# power.net
KiCad netlist of a schematic drawn in Altium Designer
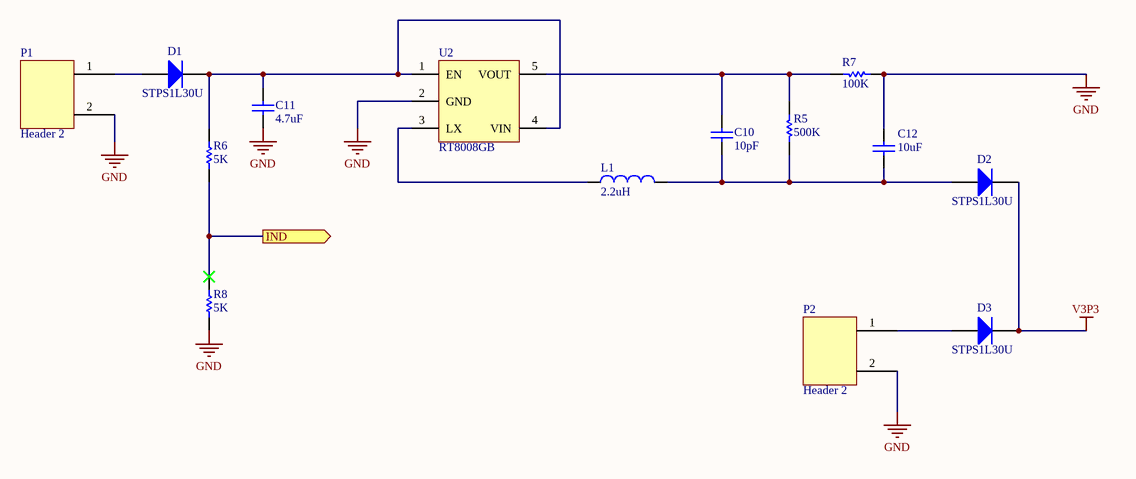
[diagram p0: power.SchDoc]

(export (version "E")
  (design (tool "Eeschema 10.0.6"))
  (components
    (comp (ref "C10")
      (value "10pF")
      (footprint "CAPACITOR")
      (description "Capacitor")
      (fields (field (name "PUBLISHER") "Altium Limited"))
      (libsource (lib "Miscellaneous Devices") (part "Cap"))
    )
    (comp (ref "C11")
      (value "4.7uF")
      (footprint "CAPACITOR")
      (description "Capacitor")
      (fields (field (name "PUBLISHER") "Altium Limited"))
      (libsource (lib "Miscellaneous Devices") (part "Cap"))
    )
    (comp (ref "C12")
      (value "10uF")
      (footprint "CAPACITOR")
      (description "Capacitor")
      (fields (field (name "PUBLISHER") "Altium Limited"))
      (libsource (lib "Miscellaneous Devices") (part "Cap"))
    )
    (comp (ref "D1")
      (value "STPS1L30U")
      (footprint "Schottky")
      (description "Diode Schottky")
      (fields (field (name "PUBLISHER") "Altium Limited"))
      (libsource (lib "Miscellaneous Devices") (part "Diode"))
    )
    (comp (ref "D2")
      (value "STPS1L30U")
      (footprint "Schottky")
      (description "Diode Schottky")
      (fields (field (name "PUBLISHER") "Altium Limited"))
      (libsource (lib "Miscellaneous Devices") (part "Diode"))
    )
    (comp (ref "D3")
      (value "STPS1L30U")
      (footprint "Schottky")
      (description "Diode Schottky")
      (fields (field (name "PUBLISHER") "Altium Limited"))
      (libsource (lib "Miscellaneous Devices") (part "Diode"))
    )
    (comp (ref "L1")
      (value "2.2uH")
      (footprint "Inductor")
      (description "Inductor")
      (fields (field (name "PUBLISHER") "Altium Limited"))
      (libsource (lib "Miscellaneous Devices") (part "Inductor"))
    )
    (comp (ref "P1")
      (value "Header 2")
      (footprint "Header 2 BATTERY")
      (libsource (lib "Klotz") (part "Header 2"))
    )
    (comp (ref "P2")
      (value "Header 2")
      (footprint "Header 2 BATTERY")
      (libsource (lib "Klotz") (part "Header 2"))
    )
    (comp (ref "R5")
      (value "500K")
      (footprint "Resistor")
      (description "Resistor")
      (fields (field (name "PUBLISHER") "Altium Limited"))
      (libsource (lib "Miscellaneous Devices") (part "Res1"))
    )
    (comp (ref "R6")
      (value "5K")
      (footprint "Resistor")
      (description "Resistor")
      (fields (field (name "PUBLISHER") "Altium Limited"))
      (libsource (lib "Miscellaneous Devices") (part "Res1"))
    )
    (comp (ref "R7")
      (value "100K")
      (footprint "Resistor")
      (description "Resistor")
      (fields (field (name "PUBLISHER") "Altium Limited"))
      (libsource (lib "Miscellaneous Devices") (part "Res1"))
    )
    (comp (ref "R8")
      (value "5K")
      (footprint "Resistor")
      (description "Resistor")
      (fields (field (name "PUBLISHER") "Altium Limited"))
      (libsource (lib "Miscellaneous Devices") (part "Res1"))
    )
    (comp (ref "U2")
      (value "RT8008GB")
      (footprint "REGULATEUR")
      (description "Voltage Regulator")
      (libsource (lib "Klotz") (part "RT8008GB"))
    )
  )
  (nets
    (net (code "1") (name "/IND") (class "Default")
      (node (ref "R6") (pin "1") (pinfunction "1_1") (pintype "passive"))
      (node (ref "R8") (pin "2") (pinfunction "2_2") (pintype "passive"))
    )
    (net (code "2") (name "GND") (class "Default")
      (node (ref "C11") (pin "1") (pinfunction "1_1") (pintype "passive"))
      (node (ref "C12") (pin "1") (pinfunction "1_1") (pintype "passive"))
      (node (ref "P1") (pin "2") (pintype "power_in"))
      (node (ref "P2") (pin "2") (pintype "power_in"))
      (node (ref "R7") (pin "2") (pinfunction "2_2") (pintype "passive"))
      (node (ref "R8") (pin "1") (pinfunction "1_1") (pintype "passive"))
      (node (ref "U2") (pin "2") (pinfunction "GND_2") (pintype "power_in"))
    )
    (net (code "3") (name "Net-(D1-A)") (class "Default")
      (node (ref "D1") (pin "1") (pinfunction "A_1") (pintype "passive"))
      (node (ref "P1") (pin "1") (pintype "power_in"))
    )
    (net (code "4") (name "Net-(D1-K)") (class "Default")
      (node (ref "C11") (pin "2") (pinfunction "2_2") (pintype "passive"))
      (node (ref "D1") (pin "2") (pinfunction "K_2") (pintype "passive"))
      (node (ref "R6") (pin "2") (pinfunction "2_2") (pintype "passive"))
      (node (ref "U2") (pin "1") (pinfunction "EN_1") (pintype "power_in"))
      (node (ref "U2") (pin "4") (pinfunction "VIN_4") (pintype "power_in"))
    )
    (net (code "5") (name "Net-(D2-A)") (class "Default")
      (node (ref "C10") (pin "2") (pinfunction "2_2") (pintype "passive"))
      (node (ref "C12") (pin "2") (pinfunction "2_2") (pintype "passive"))
      (node (ref "D2") (pin "1") (pinfunction "A_1") (pintype "passive"))
      (node (ref "L1") (pin "2") (pinfunction "2_2") (pintype "passive"))
      (node (ref "R5") (pin "2") (pinfunction "2_2") (pintype "passive"))
    )
    (net (code "6") (name "Net-(D3-A)") (class "Default")
      (node (ref "D3") (pin "1") (pinfunction "A_1") (pintype "passive"))
      (node (ref "P2") (pin "1") (pintype "power_in"))
    )
    (net (code "7") (name "Net-(U2-LX)") (class "Default")
      (node (ref "L1") (pin "1") (pinfunction "1_1") (pintype "passive"))
      (node (ref "U2") (pin "3") (pinfunction "LX_3") (pintype "power_in"))
    )
    (net (code "8") (name "Net-(U2-VOUT)") (class "Default")
      (node (ref "C10") (pin "1") (pinfunction "1_1") (pintype "passive"))
      (node (ref "R5") (pin "1") (pinfunction "1_1") (pintype "passive"))
      (node (ref "R7") (pin "1") (pinfunction "1_1") (pintype "passive"))
      (node (ref "U2") (pin "5") (pinfunction "VOUT_5") (pintype "power_in"))
    )
    (net (code "9") (name "V3P3") (class "Default")
      (node (ref "D2") (pin "2") (pinfunction "K_2") (pintype "passive"))
      (node (ref "D3") (pin "2") (pinfunction "K_2") (pintype "passive"))
    )
  )
)
